# 3_PWM_Generator.net
KiCad netlist of a schematic drawn in Altium Designer
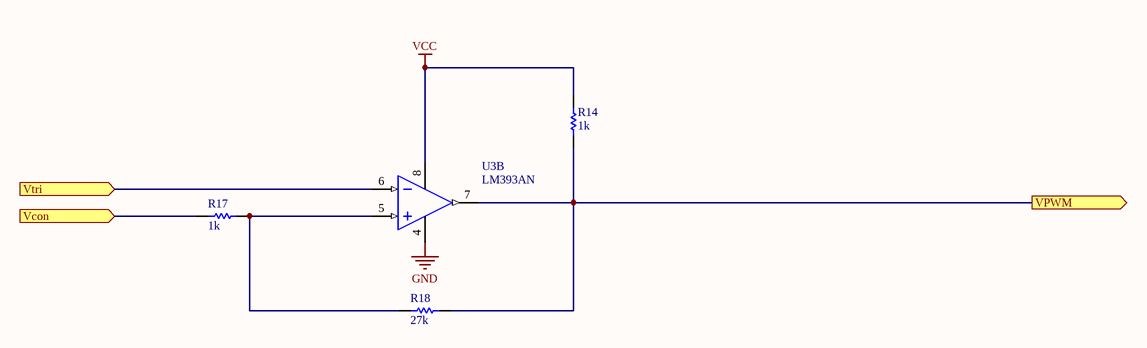
[diagram p0: 3_PWM Generator.SchDoc]

(export (version "E")
  (design (tool "Eeschema 10.0.6"))
  (components
    (comp (ref "R14")
      (value "1k")
      (footprint "ece-AXIAL0.4")
      (description "Resistor")
      (fields (field (name "PUBLISHER") "Altium Limited"))
      (libsource (lib "ece components") (part "Res1"))
    )
    (comp (ref "R17")
      (value "1k")
      (footprint "ece-AXIAL0.4")
      (description "Resistor")
      (fields (field (name "PUBLISHER") "Altium Limited"))
      (libsource (lib "ece components") (part "Res1"))
    )
    (comp (ref "R18")
      (value "27k")
      (footprint "ece-AXIAL0.4")
      (description "Resistor")
      (fields (field (name "PUBLISHER") "Altium Limited"))
      (libsource (lib "ece components") (part "Res1"))
    )
    (comp (ref "U3")
      (value "LM393AN")
      (footprint "ECE-DIP8")
      (description "Dual Comparator")
      (fields (field (name "PUBLISHER") "Altium Limited"))
      (libsource (lib "ece components") (part "LM393AN"))
    )
  )
  (nets
    (net (code "1") (name "/VPWM") (class "Default")
      (node (ref "R14") (pin "2") (pinfunction "2_2") (pintype "passive"))
      (node (ref "R18") (pin "1") (pinfunction "1_1") (pintype "passive"))
      (node (ref "U3") (pin "7") (pinfunction "OUT_7") (pintype "output"))
    )
    (net (code "2") (name "/Vcon") (class "Default")
      (node (ref "R17") (pin "2") (pinfunction "2_2") (pintype "passive"))
    )
    (net (code "3") (name "/Vtri") (class "Default")
      (node (ref "U3") (pin "6") (pinfunction "IN-_6") (pintype "input"))
    )
    (net (code "4") (name "GND") (class "Default")
      (node (ref "U3") (pin "4") (pinfunction "GND_4") (pintype "power_in"))
    )
    (net (code "5") (name "Net-(U3B-IN+)") (class "Default")
      (node (ref "R17") (pin "1") (pinfunction "1_1") (pintype "passive"))
      (node (ref "R18") (pin "2") (pinfunction "2_2") (pintype "passive"))
      (node (ref "U3") (pin "5") (pinfunction "IN+_5") (pintype "input"))
    )
    (net (code "6") (name "VCC") (class "Default")
      (node (ref "R14") (pin "1") (pinfunction "1_1") (pintype "passive"))
      (node (ref "U3") (pin "8") (pinfunction "V+_8") (pintype "power_in"))
    )
  )
)
